# 4_motor.net
KiCad netlist of a schematic drawn in Altium Designer
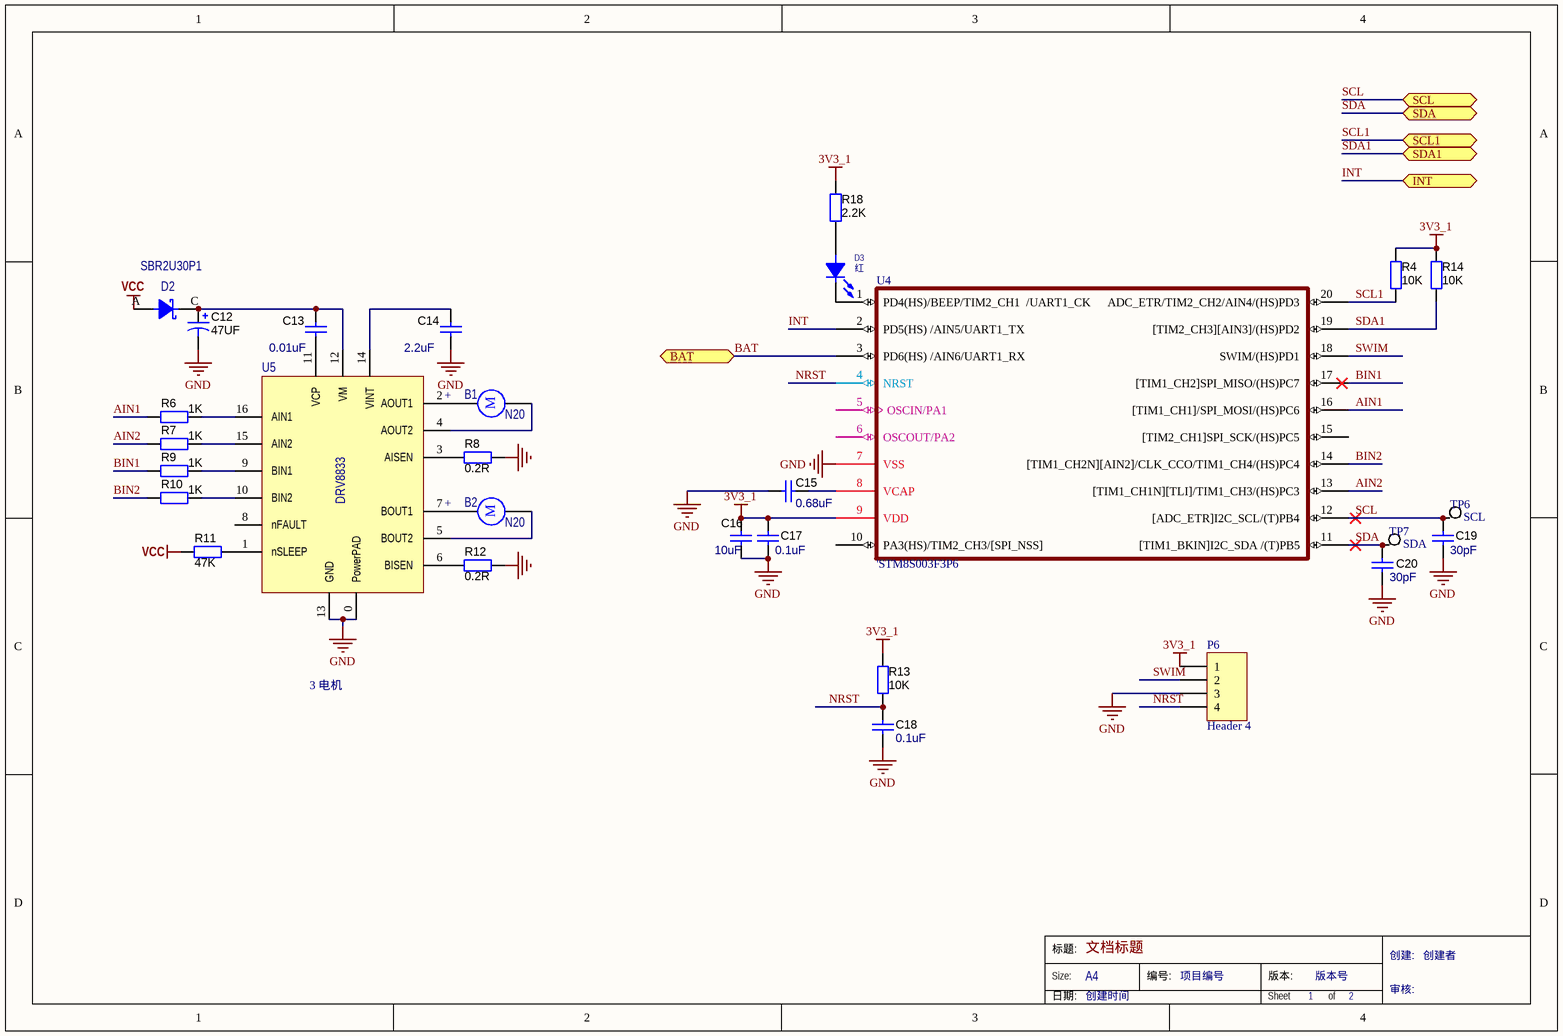
[diagram p0: 4.motor.SchDoc]

(export (version "E")
  (design (tool "Eeschema 10.0.6"))
  (components
    (comp (ref "B1")
      (value "N20")
      (footprint "2PIN/2.54MM座子")
      (description "Motor, General Kind")
      (fields (field (name "PUBLISHER") "Altium Limited"))
      (libsource (lib "Miscellaneous Devices") (part "Motor"))
    )
    (comp (ref "B2")
      (value "N20")
      (footprint "2PIN/2.54MM座子")
      (description "Motor, General Kind")
      (fields (field (name "PUBLISHER") "Altium Limited"))
      (libsource (lib "Miscellaneous Devices") (part "Motor"))
    )
    (comp (ref "C12")
      (value "47UF")
      (footprint "0805")
      (description "CAP ALUM 22UF 10V 20% SMD")
      (fields
        (field (name "PARTNUMBER") "EEE-1AA220WR")
        (field (name "MANUFACTURER") "Panasonic - ECG")
        (field (name "PUBLISHER") "National Semiconductor")
      )
      (libsource (lib "03.常用器件") (part "CAP3_pol"))
    )
    (comp (ref "C13")
      (value "0.01uF")
      (footprint "0402")
      (description "CAP, CERM, 0.01uF, 100V, +/-5%, X7R, 0603")
      (fields (field (name "PARTNUMBER") "06031C103JAT2A") (field (name "MANUFACTURER") "AVX"))
      (libsource (lib "03.常用器件") (part "CAP1_npol"))
    )
    (comp (ref "C14")
      (value "2.2uF")
      (footprint "0402")
      (description "CAP, CERM, 0.01uF, 100V, +/-5%, X7R, 0603")
      (fields (field (name "PARTNUMBER") "06031C103JAT2A") (field (name "MANUFACTURER") "AVX"))
      (libsource (lib "03.常用器件") (part "CAP1_npol"))
    )
    (comp (ref "C15")
      (value "0.68uF")
      (footprint "0402")
      (description "CAP, CERM, 0.01uF, 100V, +/-5%, X7R, 0603")
      (fields (field (name "PARTNUMBER") "06031C103JAT2A") (field (name "MANUFACTURER") "AVX"))
      (libsource (lib "03.常用器件") (part "CAP1_npol"))
    )
    (comp (ref "C16")
      (value "10uF")
      (footprint "0603")
      (description "CAP, CERM, 0.01uF, 100V, +/-5%, X7R, 0603")
      (fields (field (name "PARTNUMBER") "06031C103JAT2A") (field (name "MANUFACTURER") "AVX"))
      (libsource (lib "03.常用器件") (part "CAP1_npol"))
    )
    (comp (ref "C17")
      (value "0.1uF")
      (footprint "0402")
      (description "CAP, CERM, 0.01uF, 100V, +/-5%, X7R, 0603")
      (fields (field (name "PARTNUMBER") "06031C103JAT2A") (field (name "MANUFACTURER") "AVX"))
      (libsource (lib "03.常用器件") (part "CAP1_npol"))
    )
    (comp (ref "C18")
      (value "0.1uF")
      (footprint "0402")
      (description "CAP, CERM, 0.01uF, 100V, +/-5%, X7R, 0603")
      (fields (field (name "PARTNUMBER") "06031C103JAT2A") (field (name "MANUFACTURER") "AVX"))
      (libsource (lib "03.常用器件") (part "CAP1_npol"))
    )
    (comp (ref "C19")
      (value "30pF")
      (footprint "0402")
      (description "CAP, CERM, 0.01uF, 100V, +/-5%, X7R, 0603")
      (fields (field (name "PARTNUMBER") "06031C103JAT2A") (field (name "MANUFACTURER") "AVX"))
      (libsource (lib "03.常用器件") (part "CAP1_npol"))
    )
    (comp (ref "C20")
      (value "30pF")
      (footprint "0402")
      (description "CAP, CERM, 0.01uF, 100V, +/-5%, X7R, 0603")
      (fields (field (name "PARTNUMBER") "06031C103JAT2A") (field (name "MANUFACTURER") "AVX"))
      (libsource (lib "03.常用器件") (part "CAP1_npol"))
    )
    (comp (ref "D2")
      (value "SBR2U30P1")
      (footprint "POWERDI123")
      (fields (field (name "PARTNUMBER") "?") (field (name "PUBLISHER") "Altium Limited"))
      (libsource (lib "03.常用器件") (part "Diode_Schottky"))
    )
    (comp (ref "D3")
      (value "红")
      (footprint "0603LED")
      (fields (field (name "MANUFACTURER") "?"))
      (libsource (lib "03.常用器件") (part "LED1"))
    )
    (comp (ref "P6")
      (value "Header 4")
      (footprint "排针2.54MM/4PIN")
      (description "Header, 4-Pin")
      (fields (field (name "PUBLISHER") "Altium Limited"))
      (libsource (lib "Miscellaneous Connectors") (part "Header 4"))
    )
    (comp (ref "R4")
      (value "10K")
      (footprint "0402")
      (description "RES, 1.0k ohm, 5%, 0.1W, 0603")
      (fields
        (field (name "PARTNUMBER") "RC0603JR-071KL")
        (field (name "MANUFACTURER") "Yageo America")
        (field (name "PUBLISHER") "Texas Instruments")
      )
      (libsource (lib "") (part "RES1_2"))
    )
    (comp (ref "R6")
      (value "1K")
      (footprint "0402")
      (description "RES, 1.0k ohm, 5%, 0.1W, 0603")
      (fields
        (field (name "PARTNUMBER") "RC0603JR-071KL")
        (field (name "MANUFACTURER") "Yageo America")
        (field (name "PUBLISHER") "Texas Instruments")
      )
      (libsource (lib "03.常用器件") (part "RES1"))
    )
    (comp (ref "R7")
      (value "1K")
      (footprint "0402")
      (description "RES, 1.0k ohm, 5%, 0.1W, 0603")
      (fields
        (field (name "PARTNUMBER") "RC0603JR-071KL")
        (field (name "MANUFACTURER") "Yageo America")
        (field (name "PUBLISHER") "Texas Instruments")
      )
      (libsource (lib "03.常用器件") (part "RES1"))
    )
    (comp (ref "R8")
      (value "0.2R")
      (footprint "0603")
      (description "RES, 1.0k ohm, 5%, 0.1W, 0603")
      (fields
        (field (name "PARTNUMBER") "RC0603JR-071KL")
        (field (name "MANUFACTURER") "Yageo America")
        (field (name "PUBLISHER") "Texas Instruments")
      )
      (libsource (lib "03.常用器件") (part "RES1"))
    )
    (comp (ref "R9")
      (value "1K")
      (footprint "0402")
      (description "RES, 1.0k ohm, 5%, 0.1W, 0603")
      (fields
        (field (name "PARTNUMBER") "RC0603JR-071KL")
        (field (name "MANUFACTURER") "Yageo America")
        (field (name "PUBLISHER") "Texas Instruments")
      )
      (libsource (lib "03.常用器件") (part "RES1"))
    )
    (comp (ref "R10")
      (value "1K")
      (footprint "0402")
      (description "RES, 1.0k ohm, 5%, 0.1W, 0603")
      (fields
        (field (name "PARTNUMBER") "RC0603JR-071KL")
        (field (name "MANUFACTURER") "Yageo America")
        (field (name "PUBLISHER") "Texas Instruments")
      )
      (libsource (lib "03.常用器件") (part "RES1"))
    )
    (comp (ref "R11")
      (value "47K")
      (footprint "0402")
      (description "RES, 1.0k ohm, 5%, 0.1W, 0603")
      (fields
        (field (name "PARTNUMBER") "RC0603JR-071KL")
        (field (name "MANUFACTURER") "Yageo America")
        (field (name "PUBLISHER") "Texas Instruments")
      )
      (libsource (lib "03.常用器件") (part "RES1"))
    )
    (comp (ref "R12")
      (value "0.2R")
      (footprint "0603")
      (description "RES, 1.0k ohm, 5%, 0.1W, 0603")
      (fields
        (field (name "PARTNUMBER") "RC0603JR-071KL")
        (field (name "MANUFACTURER") "Yageo America")
        (field (name "PUBLISHER") "Texas Instruments")
      )
      (libsource (lib "03.常用器件") (part "RES1"))
    )
    (comp (ref "R13")
      (value "10K")
      (footprint "0402")
      (description "RES, 1.0k ohm, 5%, 0.1W, 0603")
      (fields
        (field (name "PARTNUMBER") "RC0603JR-071KL")
        (field (name "MANUFACTURER") "Yageo America")
        (field (name "PUBLISHER") "Texas Instruments")
      )
      (libsource (lib "") (part "RES1_1"))
    )
    (comp (ref "R14")
      (value "10K")
      (footprint "0402")
      (description "RES, 1.0k ohm, 5%, 0.1W, 0603")
      (fields
        (field (name "PARTNUMBER") "RC0603JR-071KL")
        (field (name "MANUFACTURER") "Yageo America")
        (field (name "PUBLISHER") "Texas Instruments")
      )
      (libsource (lib "") (part "RES1_2"))
    )
    (comp (ref "R18")
      (value "2.2K")
      (footprint "0402")
      (description "RES, 1.0k ohm, 5%, 0.1W, 0603")
      (fields
        (field (name "PARTNUMBER") "RC0603JR-071KL")
        (field (name "MANUFACTURER") "Yageo America")
        (field (name "PUBLISHER") "Texas Instruments")
      )
      (libsource (lib "") (part "RES1_1"))
    )
    (comp (ref "TP6")
      (value "SCL")
      (footprint "测试点")
      (description "Test Point")
      (libsource (lib "my_Schlib") (part "TP"))
    )
    (comp (ref "TP7")
      (value "SDA")
      (footprint "测试点")
      (description "Test Point")
      (libsource (lib "my_Schlib") (part "TP"))
    )
    (comp (ref "U4")
      (value "'STM8S003F3P6")
      (footprint "UFQFPN20")
      (description "ST 8-bit  Microcontroller")
      (libsource (lib "Microcontroller Unit") (part "STM8S103F2P6"))
    )
    (comp (ref "U5")
      (value "DRV8833")
      (footprint "HTSSOP -16(PWP)")
      (description "DUAL H-BRIDGE MOTOR DRIVER")
      (libsource (lib "DRV8833") (part "DRV8833PWP"))
    )
  )
  (nets
    (net (code "1") (name "/AIN1") (class "Default")
      (node (ref "R6") (pin "1") (pinfunction "1_1") (pintype "passive"))
      (node (ref "U4") (pin "16") (pinfunction "[TIM1_CH1]/SPI_MOSI/(HS)PC6_16") (pintype "bidirectional"))
    )
    (net (code "2") (name "/AIN2") (class "Default")
      (node (ref "R7") (pin "1") (pinfunction "1_1") (pintype "passive"))
      (node (ref "U4") (pin "13") (pinfunction "[TIM1_CH1N][TLI]/TIM1_CH3/(HS)PC3_13") (pintype "bidirectional"))
    )
    (net (code "3") (name "/BAT") (class "Default")
      (node (ref "U4") (pin "3") (pinfunction "PD6(HS)_/AIN6/UART1_RX_3") (pintype "bidirectional"))
    )
    (net (code "4") (name "/BIN1") (class "Default")
      (node (ref "R9") (pin "1") (pinfunction "1_1") (pintype "passive"))
      (node (ref "U4") (pin "17") (pinfunction "[TIM1_CH2]SPI_MISO/(HS)PC7_17") (pintype "bidirectional"))
    )
    (net (code "5") (name "/BIN2") (class "Default")
      (node (ref "R10") (pin "1") (pinfunction "1_1") (pintype "passive"))
      (node (ref "U4") (pin "14") (pinfunction "[TIM1_CH2N][AIN2]/CLK_CCO/TIM1_CH4/(HS)PC4_14") (pintype "bidirectional"))
    )
    (net (code "6") (name "/INT") (class "Default")
      (node (ref "U4") (pin "2") (pinfunction "PD5(HS)_/AIN5/UART1_TX_2") (pintype "bidirectional"))
    )
    (net (code "7") (name "/NRST") (class "Default")
      (node (ref "C18") (pin "2") (pinfunction "2_2") (pintype "passive"))
      (node (ref "P6") (pin "4") (pinfunction "4_4") (pintype "passive"))
      (node (ref "R13") (pin "2") (pinfunction "2_2") (pintype "passive"))
      (node (ref "U4") (pin "4") (pinfunction "NRST_4") (pintype "bidirectional"))
    )
    (net (code "9") (name "/SCL") (class "Default")
      (node (ref "C19") (pin "2") (pinfunction "2_2") (pintype "passive"))
      (node (ref "TP6") (pin "1") (pinfunction "1_1") (pintype "passive"))
      (node (ref "U4") (pin "12") (pinfunction "[ADC_ETR]I2C_SCL/(T)PB4_12") (pintype "bidirectional"))
    )
    (net (code "11") (name "/SCL1") (class "Default")
      (node (ref "R4") (pin "1") (pinfunction "1_1") (pintype "passive"))
      (node (ref "U4") (pin "20") (pinfunction "ADC_ETR/TIM2_CH2/AIN4/(HS)PD3_20") (pintype "bidirectional"))
    )
    (net (code "12") (name "/SDA") (class "Default")
      (node (ref "C20") (pin "2") (pinfunction "2_2") (pintype "passive"))
      (node (ref "TP7") (pin "1") (pinfunction "1_1") (pintype "passive"))
      (node (ref "U4") (pin "11") (pinfunction "[TIM1_BKIN]I2C_SDA_/(T)PB5_11") (pintype "bidirectional"))
    )
    (net (code "13") (name "/SDA1") (class "Default")
      (node (ref "R14") (pin "1") (pinfunction "1_1") (pintype "passive"))
      (node (ref "U4") (pin "19") (pinfunction "[TIM2_CH3][AIN3]/(HS)PD2_19") (pintype "bidirectional"))
    )
    (net (code "14") (name "/SWIM") (class "Default")
      (node (ref "P6") (pin "2") (pinfunction "2_2") (pintype "passive"))
      (node (ref "U4") (pin "18") (pinfunction "SWIM/(HS)PD1_18") (pintype "bidirectional"))
    )
    (net (code "15") (name "3V3_1") (class "Default")
      (node (ref "C16") (pin "1") (pinfunction "1_1") (pintype "passive"))
      (node (ref "C17") (pin "2") (pinfunction "2_2") (pintype "passive"))
      (node (ref "P6") (pin "1") (pinfunction "1_1") (pintype "passive"))
      (node (ref "R13") (pin "1") (pinfunction "1_1") (pintype "passive"))
      (node (ref "R14") (pin "2") (pinfunction "2_2") (pintype "passive"))
      (node (ref "R18") (pin "1") (pinfunction "1_1") (pintype "passive"))
      (node (ref "R4") (pin "2") (pinfunction "2_2") (pintype "passive"))
      (node (ref "U4") (pin "9") (pinfunction "VDD_9") (pintype "power_in"))
    )
    (net (code "16") (name "GND") (class "Default")
      (node (ref "C12") (pin "2") (pinfunction "-_2") (pintype "passive"))
      (node (ref "C14") (pin "1") (pinfunction "1_1") (pintype "passive"))
      (node (ref "C15") (pin "2") (pinfunction "2_2") (pintype "passive"))
      (node (ref "C16") (pin "2") (pinfunction "2_2") (pintype "passive"))
      (node (ref "C17") (pin "1") (pinfunction "1_1") (pintype "passive"))
      (node (ref "C18") (pin "1") (pinfunction "1_1") (pintype "passive"))
      (node (ref "C19") (pin "1") (pinfunction "1_1") (pintype "passive"))
      (node (ref "C20") (pin "1") (pinfunction "1_1") (pintype "passive"))
      (node (ref "P6") (pin "3") (pinfunction "3_3") (pintype "passive"))
      (node (ref "R12") (pin "2") (pinfunction "2_2") (pintype "passive"))
      (node (ref "R8") (pin "2") (pinfunction "2_2") (pintype "passive"))
      (node (ref "U4") (pin "7") (pinfunction "VSS_7") (pintype "power_in"))
      (node (ref "U5") (pin "0") (pinfunction "PowerPAD_0") (pintype "passive"))
      (node (ref "U5") (pin "13") (pinfunction "GND_13") (pintype "passive"))
    )
    (net (code "17") (name "Net-(C12-+)") (class "Default")
      (node (ref "C12") (pin "1") (pinfunction "+_1") (pintype "passive"))
      (node (ref "C13") (pin "2") (pinfunction "2_2") (pintype "passive"))
      (node (ref "D2") (pin "C") (pinfunction "CATHODE_C") (pintype "passive"))
      (node (ref "U5") (pin "12") (pinfunction "VM_12") (pintype "passive"))
    )
    (net (code "18") (name "Net-(D3-ANODE)") (class "Default")
      (node (ref "D3") (pin "A") (pinfunction "ANODE_A") (pintype "passive"))
      (node (ref "R18") (pin "2") (pinfunction "2_2") (pintype "passive"))
    )
    (net (code "19") (name "Net-(D3-CATHODE)") (class "Default")
      (node (ref "D3") (pin "C") (pinfunction "CATHODE_C") (pintype "passive"))
      (node (ref "U4") (pin "1") (pinfunction "PD4(HS)/BEEP/TIM2_CH1__/UART1_CK_1") (pintype "bidirectional"))
    )
    (net (code "20") (name "Net-(U4-VCAP)") (class "Default")
      (node (ref "C15") (pin "1") (pinfunction "1_1") (pintype "passive"))
      (node (ref "U4") (pin "8") (pinfunction "VCAP_8") (pintype "power_in"))
    )
    (net (code "21") (name "Net-(U5-AIN1)") (class "Default")
      (node (ref "R6") (pin "2") (pinfunction "2_2") (pintype "passive"))
      (node (ref "U5") (pin "16") (pinfunction "AIN1_16") (pintype "passive"))
    )
    (net (code "22") (name "Net-(U5-AIN2)") (class "Default")
      (node (ref "R7") (pin "2") (pinfunction "2_2") (pintype "passive"))
      (node (ref "U5") (pin "15") (pinfunction "AIN2_15") (pintype "passive"))
    )
    (net (code "23") (name "Net-(U5-AISEN)") (class "Default")
      (node (ref "R8") (pin "1") (pinfunction "1_1") (pintype "passive"))
      (node (ref "U5") (pin "3") (pinfunction "AISEN_3") (pintype "passive"))
    )
    (net (code "24") (name "Net-(U5-AOUT1)") (class "Default")
      (node (ref "B1") (pin "1") (pinfunction "1_1") (pintype "passive"))
      (node (ref "U5") (pin "2") (pinfunction "AOUT1_2") (pintype "passive"))
    )
    (net (code "25") (name "Net-(U5-AOUT2)") (class "Default")
      (node (ref "B1") (pin "2") (pinfunction "2_2") (pintype "passive"))
      (node (ref "U5") (pin "4") (pinfunction "AOUT2_4") (pintype "passive"))
    )
    (net (code "26") (name "Net-(U5-BIN1)") (class "Default")
      (node (ref "R9") (pin "2") (pinfunction "2_2") (pintype "passive"))
      (node (ref "U5") (pin "9") (pinfunction "BIN1_9") (pintype "passive"))
    )
    (net (code "27") (name "Net-(U5-BIN2)") (class "Default")
      (node (ref "R10") (pin "2") (pinfunction "2_2") (pintype "passive"))
      (node (ref "U5") (pin "10") (pinfunction "BIN2_10") (pintype "passive"))
    )
    (net (code "28") (name "Net-(U5-BISEN)") (class "Default")
      (node (ref "R12") (pin "1") (pinfunction "1_1") (pintype "passive"))
      (node (ref "U5") (pin "6") (pinfunction "BISEN_6") (pintype "passive"))
    )
    (net (code "29") (name "Net-(U5-BOUT1)") (class "Default")
      (node (ref "B2") (pin "1") (pinfunction "1_1") (pintype "passive"))
      (node (ref "U5") (pin "7") (pinfunction "BOUT1_7") (pintype "passive"))
    )
    (net (code "30") (name "Net-(U5-BOUT2)") (class "Default")
      (node (ref "B2") (pin "2") (pinfunction "2_2") (pintype "passive"))
      (node (ref "U5") (pin "5") (pinfunction "BOUT2_5") (pintype "passive"))
    )
    (net (code "31") (name "Net-(U5-VCP)") (class "Default")
      (node (ref "C13") (pin "1") (pinfunction "1_1") (pintype "passive"))
      (node (ref "U5") (pin "11") (pinfunction "VCP_11") (pintype "passive"))
    )
    (net (code "32") (name "Net-(U5-VINT)") (class "Default")
      (node (ref "C14") (pin "2") (pinfunction "2_2") (pintype "passive"))
      (node (ref "U5") (pin "14") (pinfunction "VINT_14") (pintype "passive"))
    )
    (net (code "33") (name "Net-(U5-nSLEEP)") (class "Default")
      (node (ref "R11") (pin "2") (pinfunction "2_2") (pintype "passive"))
      (node (ref "U5") (pin "1") (pinfunction "nSLEEP_1") (pintype "passive"))
    )
    (net (code "34") (name "VCC") (class "Default")
      (node (ref "D2") (pin "A") (pinfunction "ANODE_A") (pintype "passive"))
      (node (ref "R11") (pin "1") (pinfunction "1_1") (pintype "passive"))
    )
    (net (code "35") (name "unconnected-(U4-OSCIN{slash}PA1-Pad5)") (class "Default")
      (node (ref "U4") (pin "5") (pinfunction "OSCIN/PA1_5") (pintype "bidirectional"))
    )
    (net (code "36") (name "unconnected-(U4-OSCOUT{slash}PA2-Pad6)") (class "Default")
      (node (ref "U4") (pin "6") (pinfunction "OSCOUT/PA2_6") (pintype "bidirectional"))
    )
    (net (code "37") (name "unconnected-(U4-PA3(HS){slash}TIM2_CH3{slash}[SPI_NSS]-Pad10)") (class "Default")
      (node (ref "U4") (pin "10") (pinfunction "PA3(HS)/TIM2_CH3/[SPI_NSS]_10") (pintype "bidirectional"))
    )
    (net (code "38") (name "unconnected-(U4-[TIM2_CH1]SPI_SCK{slash}(HS)PC5-Pad15)") (class "Default")
      (node (ref "U4") (pin "15") (pinfunction "[TIM2_CH1]SPI_SCK/(HS)PC5_15") (pintype "bidirectional"))
    )
    (net (code "39") (name "unconnected-(U5-nFAULT-Pad8)") (class "Default")
      (node (ref "U5") (pin "8") (pinfunction "nFAULT_8") (pintype "passive"))
    )
  )
)
